# Audio_AND_HPJ.net
KiCad netlist of a schematic drawn in Altium Designer
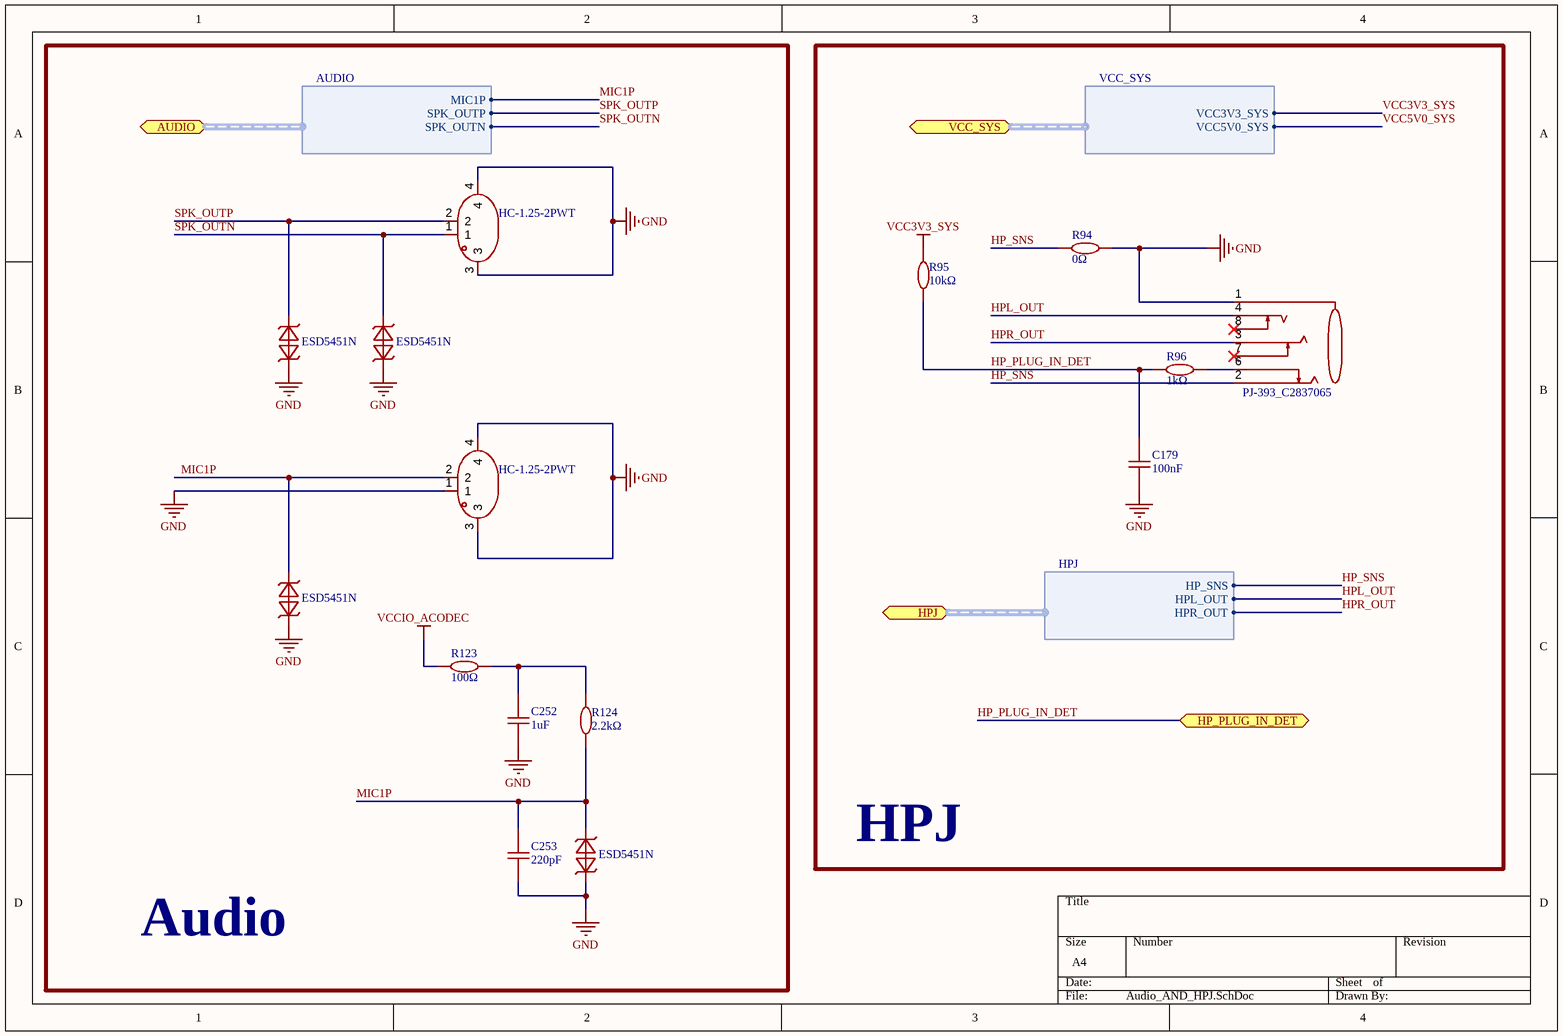
[diagram p0: Audio_AND_HPJ.SchDoc]

(export (version "E")
  (design (tool "Eeschema 10.0.6"))
  (components
    (comp (ref "AUDIO1")
      (value "PJ-393_C2837065")
      (footprint "AUDIO-SMD_PJ-393")
      (description "3.5mm耳机座 七脚四极带三组开关耳机插座；耐高温贴片耳机插座")
      (libsource (lib "Connector") (part "PJ-393_C2837065"))
    )
    (comp (ref "C179")
      (value "100nF")
      (footprint "C0402")
      (description "50V 100nF X7R ±10% 0402 Ceramic Capacitors ROHS")
      (libsource (lib "RLC") (part "100nF"))
    )
    (comp (ref "C252")
      (value "1uF")
      (footprint "C0402")
      (description "50V 1uF X5R ±10% 0402 Ceramic Capacitors ROHS")
      (libsource (lib "RLC") (part "1uF"))
    )
    (comp (ref "C253")
      (value "220pF")
      (footprint "C0402")
      (description "16V 220pF X7R ±10% 0402 Ceramic Capacitors ROHS")
      (libsource (lib "RLC") (part "220pF"))
    )
    (comp (ref "CN3")
      (value "HC-1.25-2PWT")
      (footprint "CONN-SMD_2P-P1.25-HC-1.25-2PWT")
      (description "SMD,P=1.25mm,卧贴  1x2P 间距:1.25mm 卧贴 系列:PicoBlade(MX 1.25)")
      (libsource (lib "Connector") (part "HC-1.25-2PWT"))
    )
    (comp (ref "CN4")
      (value "HC-1.25-2PWT")
      (footprint "CONN-SMD_2P-P1.25-HC-1.25-2PWT")
      (description "SMD,P=1.25mm,卧贴  1x2P 间距:1.25mm 卧贴 系列:PicoBlade(MX 1.25)")
      (libsource (lib "Connector") (part "HC-1.25-2PWT"))
    )
    (comp (ref "R94")
      (value "0Ω")
      (footprint "R0402")
      (description "0Ω 62.5mW 50V Thick Film Resistor ±1% 0402 Chip Resistor - Surface Mount ROHS")
      (libsource (lib "RLC") (part "0Ω"))
    )
    (comp (ref "R95")
      (value "10kΩ")
      (footprint "R0402")
      (description "62.5mW 10kΩ 50V ±100ppm/℃ Thick Film Resistor ±1% 0402 Chip Resistor - Surface Mount ROHS")
      (libsource (lib "RLC") (part "10kΩ"))
    )
    (comp (ref "R96")
      (value "1kΩ")
      (footprint "R0402")
      (description "1kΩ 62.5mW 50V ±100ppm/℃ Thick Film Resistor ±1% 0402 Chip Resistor - Surface Mount ROHS")
      (libsource (lib "RLC") (part "1kΩ"))
    )
    (comp (ref "R123")
      (value "100Ω")
      (footprint "R0402")
      (description "100Ω 62.5mW 50V ±100ppm/℃ Thick Film Resistor ±1% 0402 Chip Resistor - Surface Mount ROHS")
      (libsource (lib "RLC") (part "100Ω"))
    )
    (comp (ref "R124")
      (value "2.2kΩ")
      (footprint "R0402")
      (description "2.2kΩ ±1% 62.5mW 厚膜电阻")
      (libsource (lib "RLC") (part "2.2kΩ"))
    )
    (comp (ref "U23")
      (value "ESD5451N")
      (footprint "DFN1006-2L-BI")
      (description "是双向 TVS（瞬态电压抑制器），专门用于保护连接到低速数据线和控制线的敏感电子元件，使其免受 ESD（静电放电）、EFT（电快速瞬变）和浪涌引起的过应力影响。")
      (libsource (lib "LED") (part "ESD5451N"))
    )
    (comp (ref "U24")
      (value "ESD5451N")
      (footprint "DFN1006-2L-BI")
      (description "是双向 TVS（瞬态电压抑制器），专门用于保护连接到低速数据线和控制线的敏感电子元件，使其免受 ESD（静电放电）、EFT（电快速瞬变）和浪涌引起的过应力影响。")
      (libsource (lib "LED") (part "ESD5451N"))
    )
    (comp (ref "U25")
      (value "ESD5451N")
      (footprint "DFN1006-2L-BI")
      (description "是双向 TVS（瞬态电压抑制器），专门用于保护连接到低速数据线和控制线的敏感电子元件，使其免受 ESD（静电放电）、EFT（电快速瞬变）和浪涌引起的过应力影响。")
      (libsource (lib "LED") (part "ESD5451N"))
    )
    (comp (ref "U26")
      (value "ESD5451N")
      (footprint "DFN1006-2L-BI")
      (description "是双向 TVS（瞬态电压抑制器），专门用于保护连接到低速数据线和控制线的敏感电子元件，使其免受 ESD（静电放电）、EFT（电快速瞬变）和浪涌引起的过应力影响。")
      (libsource (lib "LED") (part "ESD5451N"))
    )
  )
  (nets
    (net (code "4") (name "/HPL_OUT") (class "Default")
      (node (ref "AUDIO1") (pin "4") (pinfunction "4_4") (pintype "passive"))
    )
    (net (code "5") (name "/HPR_OUT") (class "Default")
      (node (ref "AUDIO1") (pin "3") (pinfunction "3_3") (pintype "passive"))
    )
    (net (code "6") (name "/HP_PLUG_IN_DET") (class "Default")
      (node (ref "C179") (pin "2") (pinfunction "2_2") (pintype "passive"))
      (node (ref "R95") (pin "1") (pinfunction "1_1") (pintype "passive"))
      (node (ref "R96") (pin "1") (pinfunction "1_1") (pintype "passive"))
    )
    (net (code "7") (name "/HP_SNS") (class "Default")
      (node (ref "AUDIO1") (pin "2") (pinfunction "2_2") (pintype "passive"))
      (node (ref "R94") (pin "1") (pinfunction "1_1") (pintype "passive"))
    )
    (net (code "8") (name "/MIC1P") (class "Default")
      (node (ref "C253") (pin "2") (pinfunction "2_2") (pintype "passive"))
      (node (ref "CN4") (pin "2") (pinfunction "2_2") (pintype "passive"))
      (node (ref "R124") (pin "1") (pinfunction "1_1") (pintype "passive"))
      (node (ref "U25") (pin "2") (pinfunction "2_2") (pintype "passive"))
      (node (ref "U26") (pin "2") (pinfunction "2_2") (pintype "passive"))
    )
    (net (code "9") (name "/SPK_OUTN") (class "Default")
      (node (ref "CN3") (pin "1") (pinfunction "1_1") (pintype "passive"))
      (node (ref "U24") (pin "2") (pinfunction "2_2") (pintype "passive"))
    )
    (net (code "10") (name "/SPK_OUTP") (class "Default")
      (node (ref "CN3") (pin "2") (pinfunction "2_2") (pintype "passive"))
      (node (ref "U23") (pin "2") (pinfunction "2_2") (pintype "passive"))
    )
    (net (code "15") (name "GND") (class "Default")
      (node (ref "AUDIO1") (pin "1") (pinfunction "1_1") (pintype "passive"))
      (node (ref "C179") (pin "1") (pinfunction "1_1") (pintype "passive"))
      (node (ref "C252") (pin "1") (pinfunction "1_1") (pintype "passive"))
      (node (ref "C253") (pin "1") (pinfunction "1_1") (pintype "passive"))
      (node (ref "CN3") (pin "3") (pinfunction "3_3") (pintype "passive"))
      (node (ref "CN3") (pin "4") (pinfunction "4_4") (pintype "passive"))
      (node (ref "CN4") (pin "1") (pinfunction "1_1") (pintype "passive"))
      (node (ref "CN4") (pin "3") (pinfunction "3_3") (pintype "passive"))
      (node (ref "CN4") (pin "4") (pinfunction "4_4") (pintype "passive"))
      (node (ref "R94") (pin "2") (pinfunction "2_2") (pintype "passive"))
      (node (ref "U23") (pin "1") (pinfunction "1_1") (pintype "passive"))
      (node (ref "U24") (pin "1") (pinfunction "1_1") (pintype "passive"))
      (node (ref "U25") (pin "1") (pinfunction "1_1") (pintype "passive"))
      (node (ref "U26") (pin "1") (pinfunction "1_1") (pintype "passive"))
    )
    (net (code "16") (name "Net-(AUDIO1-Pad6)") (class "Default")
      (node (ref "AUDIO1") (pin "6") (pinfunction "6_6") (pintype "passive"))
      (node (ref "R96") (pin "2") (pinfunction "2_2") (pintype "passive"))
    )
    (net (code "17") (name "Net-(C252-Pad2)") (class "Default")
      (node (ref "C252") (pin "2") (pinfunction "2_2") (pintype "passive"))
      (node (ref "R123") (pin "2") (pinfunction "2_2") (pintype "passive"))
      (node (ref "R124") (pin "2") (pinfunction "2_2") (pintype "passive"))
    )
    (net (code "18") (name "VCC3V3_SYS") (class "Default")
      (node (ref "R95") (pin "2") (pinfunction "2_2") (pintype "passive"))
    )
    (net (code "19") (name "VCCIO_ACODEC") (class "Default")
      (node (ref "R123") (pin "1") (pinfunction "1_1") (pintype "passive"))
    )
    (net (code "20") (name "unconnected-(AUDIO1-Pad7)") (class "Default")
      (node (ref "AUDIO1") (pin "7") (pinfunction "7_7") (pintype "passive+no_connect"))
    )
    (net (code "21") (name "unconnected-(AUDIO1-Pad8)") (class "Default")
      (node (ref "AUDIO1") (pin "8") (pinfunction "8_8") (pintype "passive+no_connect"))
    )
  )
)
